# lab10.net
KiCad netlist of a schematic drawn in Altium Designer
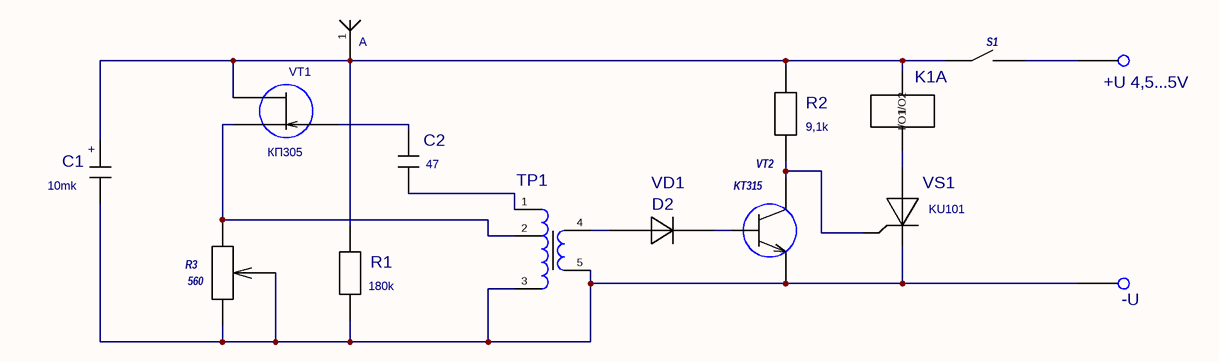
[diagram p0: lab10.SCHDOC]

(export (version "E")
  (design (tool "Eeschema 10.0.6"))
  (components
    (comp (ref "1") (value "A") (footprint "A") (libsource (lib "*") (part "A")))
    (comp (ref "2")
      (value "+U 4,5...5V")
      (footprint "A")
      (description "XT_1")
      (libsource (lib "*") (part "XT_1"))
    )
    (comp (ref "3") (value "-U") (footprint "A") (description "XT_1") (libsource (lib "*") (part "XT_1")))
    (comp (ref "C1")
      (value "10mk")
      (footprint "CAP2")
      (description "CAP2")
      (libsource (lib "*") (part "CAP2"))
    )
    (comp (ref "C2") (value "47") (footprint "CAP1") (description "CAP1") (libsource (lib "*") (part "CAP1")))
    (comp (ref "K1") (value "КУЦ1") (footprint "KUZ1") (libsource (lib "*") (part "КУЦ1")))
    (comp (ref "R1") (value "180k") (footprint "RES") (description "RES") (libsource (lib "*") (part "RES")))
    (comp (ref "R2") (value "9,1k") (footprint "RES") (description "RES") (libsource (lib "*") (part "RES")))
    (comp (ref "R3")
      (value "560")
      (footprint "СП3-38В")
      (description "СП3-38В")
      (libsource (lib "*") (part "СП3-38В"))
    )
    (comp (ref "S1") (value "T1") (footprint "Т1") (libsource (lib "*") (part "T1")))
    (comp (ref "TP1")
      (value "TRANSMORMATOR")
      (footprint "TRANSFORMATOR")
      (libsource (lib "*") (part "TRANSMORMATOR"))
    )
    (comp (ref "VD1") (value "D2") (footprint "D2") (libsource (lib "*") (part "D2")))
    (comp (ref "VS1") (value "KU101") (footprint "KU101") (libsource (lib "*") (part "KU101")))
    (comp (ref "VT1") (value "КП305") (footprint "КП305") (libsource (lib "*") (part "КП305")))
    (comp (ref "VT2") (value "KT315") (footprint "КT315") (libsource (lib "*") (part "KT315")))
  )
  (nets
    (net (code "1") (name "Net-(2-Pad1)") (class "Default")
      (node (ref "2") (pin "1") (pinfunction "1_1") (pintype "passive"))
      (node (ref "S1") (pin "2") (pinfunction "2_2") (pintype "passive"))
    )
    (net (code "2") (name "Net-(C2-Pad1)") (class "Default")
      (node (ref "C2") (pin "1") (pinfunction "1_1") (pintype "passive"))
      (node (ref "TP1") (pin "1") (pinfunction "1_1") (pintype "passive"))
    )
    (net (code "3") (name "Net-(C2-Pad2)") (class "Default")
      (node (ref "C2") (pin "2") (pinfunction "2_2") (pintype "passive"))
      (node (ref "VT1") (pin "3") (pinfunction "3_3") (pintype "passive"))
    )
    (net (code "4") (name "Net-(K1-I{slash}O1)") (class "Default")
      (node (ref "K1") (pin "1") (pinfunction "I/O1_1") (pintype "passive"))
      (node (ref "VS1") (pin "1") (pinfunction "I/OA_1") (pintype "passive"))
    )
    (net (code "5") (name "Net-(K1-I{slash}O2)") (class "Default")
      (node (ref "1") (pin "1") (pintype "passive"))
      (node (ref "C1") (pin "1") (pinfunction "1_1") (pintype "passive"))
      (node (ref "K1") (pin "2") (pinfunction "I/O2_2") (pintype "passive"))
      (node (ref "R1") (pin "2") (pintype "passive"))
      (node (ref "R2") (pin "2") (pintype "passive"))
      (node (ref "S1") (pin "1") (pinfunction "1_1") (pintype "passive"))
      (node (ref "VT1") (pin "2") (pinfunction "2_2") (pintype "passive"))
    )
    (net (code "6") (name "Net-(R3-Pad1)") (class "Default")
      (node (ref "R3") (pin "1") (pinfunction "1_1") (pintype "passive"))
      (node (ref "TP1") (pin "2") (pinfunction "2_2") (pintype "passive"))
      (node (ref "VT1") (pin "1") (pinfunction "1_1") (pintype "passive"))
    )
    (net (code "7") (name "Net-(VD1-A)") (class "Default")
      (node (ref "TP1") (pin "4") (pinfunction "4_4") (pintype "passive"))
      (node (ref "VD1") (pin "2") (pinfunction "A_2") (pintype "passive"))
    )
    (net (code "8") (name "Net-(VD1-K)") (class "Default")
      (node (ref "VD1") (pin "1") (pinfunction "K_1") (pintype "passive"))
      (node (ref "VT2") (pin "1") (pinfunction "1_1") (pintype "passive"))
    )
    (net (code "9") (name "Net-(VS1-IN)") (class "Default")
      (node (ref "R2") (pin "1") (pintype "passive"))
      (node (ref "VS1") (pin "3") (pinfunction "IN_3") (pintype "passive"))
      (node (ref "VT2") (pin "2") (pinfunction "2_2") (pintype "passive"))
    )
    (net (code "10") (name "Net-(VS1-I{slash}OB)") (class "Default")
      (node (ref "3") (pin "1") (pinfunction "1_1") (pintype "passive"))
      (node (ref "C1") (pin "2") (pinfunction "2_2") (pintype "passive"))
      (node (ref "R1") (pin "1") (pintype "passive"))
      (node (ref "R3") (pin "2") (pinfunction "2_2") (pintype "passive"))
      (node (ref "R3") (pin "3") (pinfunction "3_3") (pintype "passive"))
      (node (ref "TP1") (pin "3") (pinfunction "3_3") (pintype "passive"))
      (node (ref "TP1") (pin "5") (pinfunction "5_5") (pintype "passive"))
      (node (ref "VS1") (pin "2") (pinfunction "I/OB_2") (pintype "passive"))
      (node (ref "VT2") (pin "3") (pinfunction "3_3") (pintype "passive"))
    )
  )
)
